# Schematic.net
KiCad netlist of a schematic drawn in Altium Designer
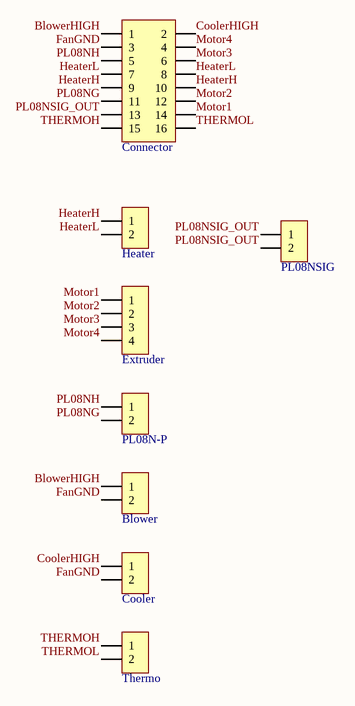
[diagram p0: Schematic.SchDoc]

(export (version "E")
  (design (tool "Eeschema 10.0.6"))
  (components
    (comp (ref "Blower")
      (value "HDR-1X2")
      (footprint "XH2.54-LI-2P")
      (description "2P接插件")
      (fields (field (name "版权归属") "封装库来自淘宝 ID：黄晶宝石"))
      (libsource (lib "5.4 - 接插件-脚距2.54 (100mil) ") (part "Header 2"))
    )
    (comp (ref "Connector")
      (value "Header 8X2")
      (footprint "IDC2.54-LI-2x8P")
      (description "8*2P接插件")
      (fields (field (name "版权归属") "封装库来自淘宝 ID：黄晶宝石"))
      (libsource (lib "5.4 - 接插件-脚距2.54 (100mil) ") (part "Header 8X2"))
    )
    (comp (ref "Cooler")
      (value "HDR-1X2")
      (footprint "XH2.54-LI-2P")
      (description "2P接插件")
      (fields (field (name "版权归属") "封装库来自淘宝 ID：黄晶宝石"))
      (libsource (lib "5.4 - 接插件-脚距2.54 (100mil) ") (part "Header 2"))
    )
    (comp (ref "Extruder")
      (value "HDR-1X4")
      (footprint "XH2.54-LI-4P")
      (description "4P接插件")
      (fields (field (name "版权归属") "封装库来自淘宝 ID：黄晶宝石"))
      (libsource (lib "5.4 - 接插件-脚距2.54 (100mil) ") (part "Header 4"))
    )
    (comp (ref "Heater")
      (value "HDR-1X2")
      (footprint "KF128-5.08-2P")
      (description "2P接插件")
      (fields (field (name "版权归属") "封装库来自淘宝卖家 ID：黄晶宝石"))
      (libsource (lib "6.1 - 接插件-脚距5.08 (200mil) ") (part "Header 2"))
    )
    (comp (ref "PL08N-P")
      (value "HDR-1X2")
      (footprint "XH2.54-LI-2P")
      (description "2P接插件")
      (fields (field (name "版权归属") "封装库来自淘宝 ID：黄晶宝石"))
      (libsource (lib "5.4 - 接插件-脚距2.54 (100mil) ") (part "Header 2"))
    )
    (comp (ref "PL08NSIG")
      (value "HDR-1X2")
      (footprint "KF2510-LI-2P")
      (description "2P接插件")
      (fields (field (name "版权归属") "封装库来自淘宝 ID：黄晶宝石"))
      (libsource (lib "5.4 - 接插件-脚距2.54 (100mil) ") (part "Header 2"))
    )
    (comp (ref "Thermo")
      (value "HDR-1X2")
      (footprint "XH2.54-LI-2P")
      (description "2P接插件")
      (fields (field (name "版权归属") "封装库来自淘宝 ID：黄晶宝石"))
      (libsource (lib "5.4 - 接插件-脚距2.54 (100mil) ") (part "Header 2"))
    )
  )
  (nets
    (net (code "1") (name "/BlowerHIGH") (class "Default")
      (node (ref "Blower") (pin "1") (pinfunction "1_1") (pintype "passive"))
      (node (ref "Connector") (pin "1") (pinfunction "1_1") (pintype "passive"))
    )
    (net (code "2") (name "/CoolerHIGH") (class "Default")
      (node (ref "Connector") (pin "2") (pinfunction "2_2") (pintype "passive"))
      (node (ref "Cooler") (pin "1") (pinfunction "1_1") (pintype "passive"))
    )
    (net (code "3") (name "/FanGND") (class "Default")
      (node (ref "Blower") (pin "2") (pinfunction "2_2") (pintype "passive"))
      (node (ref "Connector") (pin "3") (pinfunction "3_3") (pintype "passive"))
      (node (ref "Cooler") (pin "2") (pinfunction "2_2") (pintype "passive"))
    )
    (net (code "4") (name "/HeaterH") (class "Default")
      (node (ref "Connector") (pin "10") (pinfunction "10_10") (pintype "passive"))
      (node (ref "Connector") (pin "9") (pinfunction "9_9") (pintype "passive"))
      (node (ref "Heater") (pin "1") (pinfunction "1_1") (pintype "passive"))
    )
    (net (code "5") (name "/HeaterL") (class "Default")
      (node (ref "Connector") (pin "7") (pinfunction "7_7") (pintype "passive"))
      (node (ref "Connector") (pin "8") (pinfunction "8_8") (pintype "passive"))
      (node (ref "Heater") (pin "2") (pinfunction "2_2") (pintype "passive"))
    )
    (net (code "6") (name "/Motor1") (class "Default")
      (node (ref "Connector") (pin "14") (pinfunction "14_14") (pintype "passive"))
      (node (ref "Extruder") (pin "1") (pinfunction "1_1") (pintype "passive"))
    )
    (net (code "7") (name "/Motor2") (class "Default")
      (node (ref "Connector") (pin "12") (pinfunction "12_12") (pintype "passive"))
      (node (ref "Extruder") (pin "2") (pinfunction "2_2") (pintype "passive"))
    )
    (net (code "8") (name "/Motor3") (class "Default")
      (node (ref "Connector") (pin "6") (pinfunction "6_6") (pintype "passive"))
      (node (ref "Extruder") (pin "3") (pinfunction "3_3") (pintype "passive"))
    )
    (net (code "9") (name "/Motor4") (class "Default")
      (node (ref "Connector") (pin "4") (pinfunction "4_4") (pintype "passive"))
      (node (ref "Extruder") (pin "4") (pinfunction "4_4") (pintype "passive"))
    )
    (net (code "10") (name "/PL08NG") (class "Default")
      (node (ref "Connector") (pin "11") (pinfunction "11_11") (pintype "passive"))
      (node (ref "PL08N-P") (pin "2") (pinfunction "2_2") (pintype "passive"))
    )
    (net (code "11") (name "/PL08NH") (class "Default")
      (node (ref "Connector") (pin "5") (pinfunction "5_5") (pintype "passive"))
      (node (ref "PL08N-P") (pin "1") (pinfunction "1_1") (pintype "passive"))
    )
    (net (code "12") (name "/PL08NSIG_OUT") (class "Default")
      (node (ref "Connector") (pin "13") (pinfunction "13_13") (pintype "passive"))
      (node (ref "PL08NSIG") (pin "1") (pinfunction "1_1") (pintype "passive"))
      (node (ref "PL08NSIG") (pin "2") (pinfunction "2_2") (pintype "passive"))
    )
    (net (code "13") (name "/THERMOH") (class "Default")
      (node (ref "Connector") (pin "15") (pinfunction "15_15") (pintype "passive"))
      (node (ref "Thermo") (pin "1") (pinfunction "1_1") (pintype "passive"))
    )
    (net (code "14") (name "/THERMOL") (class "Default")
      (node (ref "Connector") (pin "16") (pinfunction "16_16") (pintype "passive"))
      (node (ref "Thermo") (pin "2") (pinfunction "2_2") (pintype "passive"))
    )
  )
)
